# M-Button.net
KiCad netlist of a schematic drawn in EAGLE
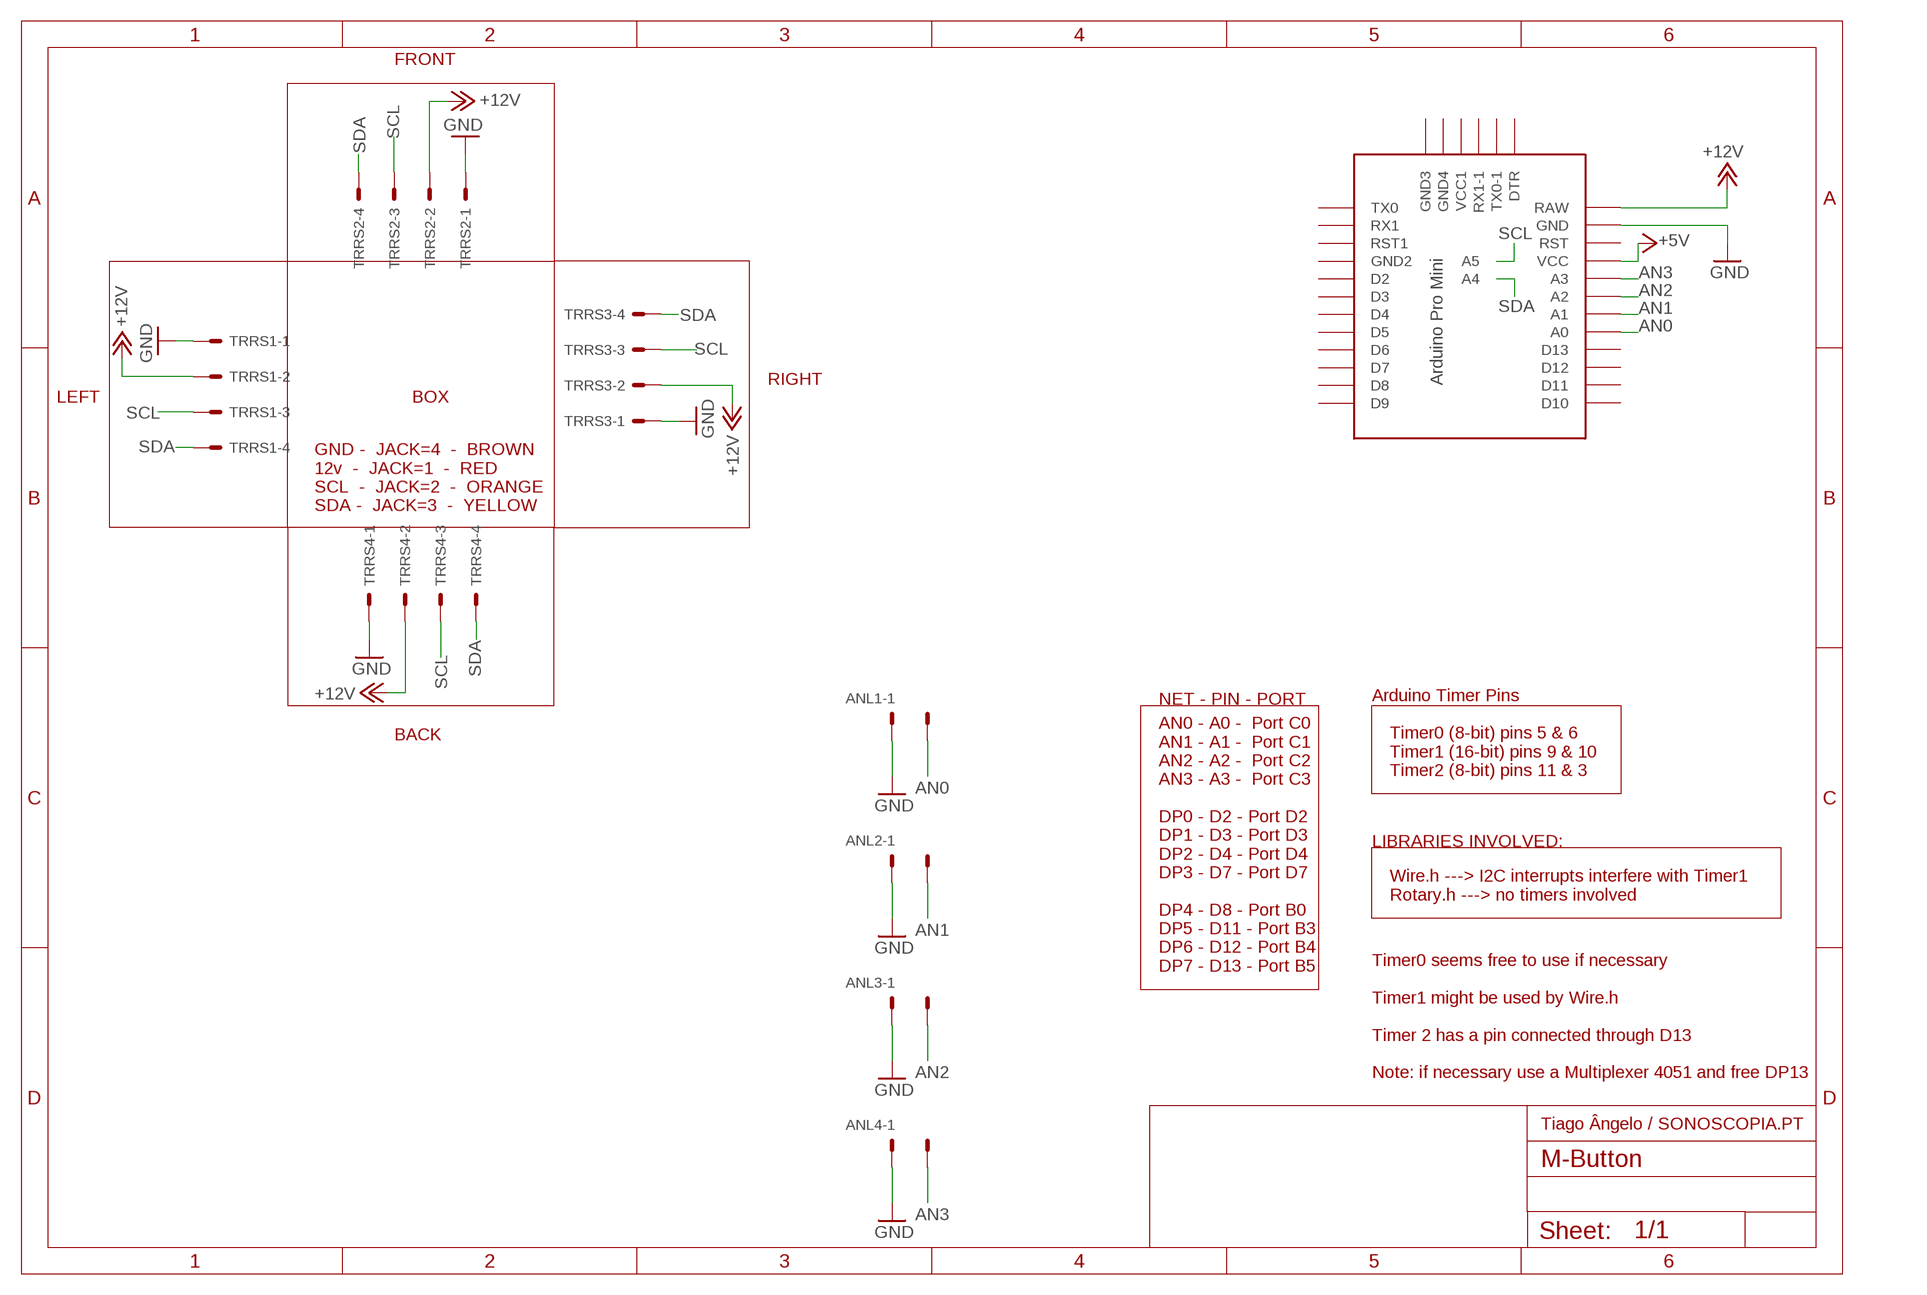
[diagram p0: schematic, sheet 1]

(export (version "E")
  (design (tool "Eeschema 10.0.6"))
  (components
    (comp (ref "ANL1")
      (value "22-27-2031-03")
      (footprint "eagle-import:6410-03")
      (libsource (lib "eagle-import") (part "22-?-0327-2031"))
    )
    (comp (ref "ANL2")
      (value "22-27-2031-03")
      (footprint "eagle-import:6410-03")
      (libsource (lib "eagle-import") (part "22-?-0327-2031"))
    )
    (comp (ref "ANL3")
      (value "22-27-2031-03")
      (footprint "eagle-import:6410-03")
      (libsource (lib "eagle-import") (part "22-?-0327-2031"))
    )
    (comp (ref "ANL4")
      (value "22-27-2031-03")
      (footprint "eagle-import:6410-03")
      (libsource (lib "eagle-import") (part "22-?-0327-2031"))
    )
    (comp (ref "TRRS1")
      (value "22-27-2041-04")
      (footprint "eagle-import:6410-04")
      (libsource (lib "eagle-import") (part "22-?-0427-2041"))
    )
    (comp (ref "TRRS2")
      (value "22-27-2041-04")
      (footprint "eagle-import:6410-04")
      (libsource (lib "eagle-import") (part "22-?-0427-2041"))
    )
    (comp (ref "TRRS3")
      (value "22-27-2041-04")
      (footprint "eagle-import:6410-04")
      (libsource (lib "eagle-import") (part "22-?-0427-2041"))
    )
    (comp (ref "TRRS4")
      (value "22-27-2041-04")
      (footprint "eagle-import:6410-04")
      (libsource (lib "eagle-import") (part "22-?-0427-2041"))
    )
    (comp (ref "U$1")
      (value "PRO-MINI-2")
      (footprint "eagle-import:PRO-MINI-2")
      (libsource (lib "eagle-import") (part "PRO-MINI-2"))
    )
  )
  (nets
    (net (code "1") (name "+5V") (class "Default")
      (node (ref "U$1") (pin "VCC") (pinfunction "VCC_VCC") (pintype "bidirectional"))
    )
    (net (code "2") (name "+12V") (class "Default")
      (node (ref "TRRS1") (pin "2") (pinfunction "S_2") (pintype "passive"))
      (node (ref "TRRS2") (pin "2") (pinfunction "S_2") (pintype "passive"))
      (node (ref "TRRS3") (pin "2") (pinfunction "S_2") (pintype "passive"))
      (node (ref "TRRS4") (pin "2") (pinfunction "S_2") (pintype "passive"))
      (node (ref "U$1") (pin "RAW") (pinfunction "RAW_RAW") (pintype "bidirectional"))
    )
    (net (code "3") (name "/AN0") (class "Default")
      (node (ref "ANL1") (pin "2") (pinfunction "S_2") (pintype "passive"))
      (node (ref "U$1") (pin "A0") (pinfunction "A0_A0") (pintype "bidirectional"))
    )
    (net (code "4") (name "/AN1") (class "Default")
      (node (ref "ANL2") (pin "2") (pinfunction "S_2") (pintype "passive"))
      (node (ref "U$1") (pin "A1") (pinfunction "A1_A1") (pintype "bidirectional"))
    )
    (net (code "5") (name "/AN2") (class "Default")
      (node (ref "ANL3") (pin "2") (pinfunction "S_2") (pintype "passive"))
      (node (ref "U$1") (pin "A2") (pinfunction "A2_A2") (pintype "bidirectional"))
    )
    (net (code "6") (name "/AN3") (class "Default")
      (node (ref "ANL4") (pin "2") (pinfunction "S_2") (pintype "passive"))
      (node (ref "U$1") (pin "A3") (pinfunction "A3_A3") (pintype "bidirectional"))
    )
    (net (code "7") (name "/SCL") (class "Default")
      (node (ref "TRRS1") (pin "3") (pinfunction "S_3") (pintype "passive"))
      (node (ref "TRRS2") (pin "3") (pinfunction "S_3") (pintype "passive"))
      (node (ref "TRRS3") (pin "3") (pinfunction "S_3") (pintype "passive"))
      (node (ref "TRRS4") (pin "3") (pinfunction "S_3") (pintype "passive"))
      (node (ref "U$1") (pin "A5") (pinfunction "A5_A5") (pintype "bidirectional"))
    )
    (net (code "8") (name "/SDA") (class "Default")
      (node (ref "TRRS1") (pin "4") (pinfunction "S_4") (pintype "passive"))
      (node (ref "TRRS2") (pin "4") (pinfunction "S_4") (pintype "passive"))
      (node (ref "TRRS3") (pin "4") (pinfunction "S_4") (pintype "passive"))
      (node (ref "TRRS4") (pin "4") (pinfunction "S_4") (pintype "passive"))
      (node (ref "U$1") (pin "A4") (pinfunction "A4_A4") (pintype "bidirectional"))
    )
    (net (code "9") (name "GND") (class "Default")
      (node (ref "ANL1") (pin "1") (pinfunction "S_1") (pintype "passive"))
      (node (ref "ANL2") (pin "1") (pinfunction "S_1") (pintype "passive"))
      (node (ref "ANL3") (pin "1") (pinfunction "S_1") (pintype "passive"))
      (node (ref "ANL4") (pin "1") (pinfunction "S_1") (pintype "passive"))
      (node (ref "TRRS1") (pin "1") (pinfunction "S_1") (pintype "passive"))
      (node (ref "TRRS2") (pin "1") (pinfunction "S_1") (pintype "passive"))
      (node (ref "TRRS3") (pin "1") (pinfunction "S_1") (pintype "passive"))
      (node (ref "TRRS4") (pin "1") (pinfunction "S_1") (pintype "passive"))
      (node (ref "U$1") (pin "GND") (pinfunction "GND_GND") (pintype "bidirectional"))
    )
    (net (code "10") (name "unconnected-(U$1-GND2-PadGND1)") (class "Default")
      (node (ref "U$1") (pin "GND1") (pinfunction "GND2_GND1") (pintype "bidirectional"))
    )
    (net (code "11") (name "unconnected-(U$1-GND3-PadGND2)") (class "Default")
      (node (ref "U$1") (pin "GND2") (pinfunction "GND3_GND2") (pintype "bidirectional"))
    )
    (net (code "12") (name "unconnected-(U$1-GND4-PadGND3)") (class "Default")
      (node (ref "U$1") (pin "GND3") (pinfunction "GND4_GND3") (pintype "bidirectional"))
    )
    (net (code "13") (name "unconnected-(U$1-PadD2)") (class "Default")
      (node (ref "U$1") (pin "D2") (pinfunction "D2_D2") (pintype "bidirectional"))
    )
    (net (code "14") (name "unconnected-(U$1-PadD3)") (class "Default")
      (node (ref "U$1") (pin "D3") (pinfunction "D3_D3") (pintype "bidirectional"))
    )
    (net (code "15") (name "unconnected-(U$1-PadD4)") (class "Default")
      (node (ref "U$1") (pin "D4") (pinfunction "D4_D4") (pintype "bidirectional"))
    )
    (net (code "16") (name "unconnected-(U$1-PadD5)") (class "Default")
      (node (ref "U$1") (pin "D5") (pinfunction "D5_D5") (pintype "bidirectional"))
    )
    (net (code "17") (name "unconnected-(U$1-PadD6)") (class "Default")
      (node (ref "U$1") (pin "D6") (pinfunction "D6_D6") (pintype "bidirectional"))
    )
    (net (code "18") (name "unconnected-(U$1-PadD7)") (class "Default")
      (node (ref "U$1") (pin "D7") (pinfunction "D7_D7") (pintype "bidirectional"))
    )
    (net (code "19") (name "unconnected-(U$1-PadD8)") (class "Default")
      (node (ref "U$1") (pin "D8") (pinfunction "D8_D8") (pintype "bidirectional"))
    )
    (net (code "20") (name "unconnected-(U$1-PadD9)") (class "Default")
      (node (ref "U$1") (pin "D9") (pinfunction "D9_D9") (pintype "bidirectional"))
    )
    (net (code "21") (name "unconnected-(U$1-PadD10)") (class "Default")
      (node (ref "U$1") (pin "D10") (pinfunction "D10_D10") (pintype "bidirectional"))
    )
    (net (code "22") (name "unconnected-(U$1-PadD11)") (class "Default")
      (node (ref "U$1") (pin "D11") (pinfunction "D11_D11") (pintype "bidirectional"))
    )
    (net (code "23") (name "unconnected-(U$1-PadD12)") (class "Default")
      (node (ref "U$1") (pin "D12") (pinfunction "D12_D12") (pintype "bidirectional"))
    )
    (net (code "24") (name "unconnected-(U$1-PadD13)") (class "Default")
      (node (ref "U$1") (pin "D13") (pinfunction "D13_D13") (pintype "bidirectional"))
    )
    (net (code "25") (name "unconnected-(U$1-PadDTR)") (class "Default")
      (node (ref "U$1") (pin "DTR") (pinfunction "DTR_DTR") (pintype "bidirectional"))
    )
    (net (code "26") (name "unconnected-(U$1-PadRST)") (class "Default")
      (node (ref "U$1") (pin "RST") (pinfunction "RST_RST") (pintype "bidirectional"))
    )
    (net (code "27") (name "unconnected-(U$1-PadRST1)") (class "Default")
      (node (ref "U$1") (pin "RST1") (pinfunction "RST1_RST1") (pintype "bidirectional"))
    )
    (net (code "28") (name "unconnected-(U$1-PadRX1)") (class "Default")
      (node (ref "U$1") (pin "RX1") (pinfunction "RX1_RX1") (pintype "bidirectional"))
    )
    (net (code "29") (name "unconnected-(U$1-PadRX1-1)") (class "Default")
      (node (ref "U$1") (pin "RX1-1") (pinfunction "RX1-1_RX1-1") (pintype "bidirectional"))
    )
    (net (code "30") (name "unconnected-(U$1-PadTX0)") (class "Default")
      (node (ref "U$1") (pin "TX0") (pinfunction "TX0_TX0") (pintype "bidirectional"))
    )
    (net (code "31") (name "unconnected-(U$1-PadTX0-1)") (class "Default")
      (node (ref "U$1") (pin "TX0-1") (pinfunction "TX0-1_TX0-1") (pintype "bidirectional"))
    )
    (net (code "32") (name "unconnected-(U$1-PadVCC1)") (class "Default")
      (node (ref "U$1") (pin "VCC1") (pinfunction "VCC1_VCC1") (pintype "bidirectional"))
    )
  )
)
